# core_v1.net
KiCad netlist of a schematic drawn in EAGLE
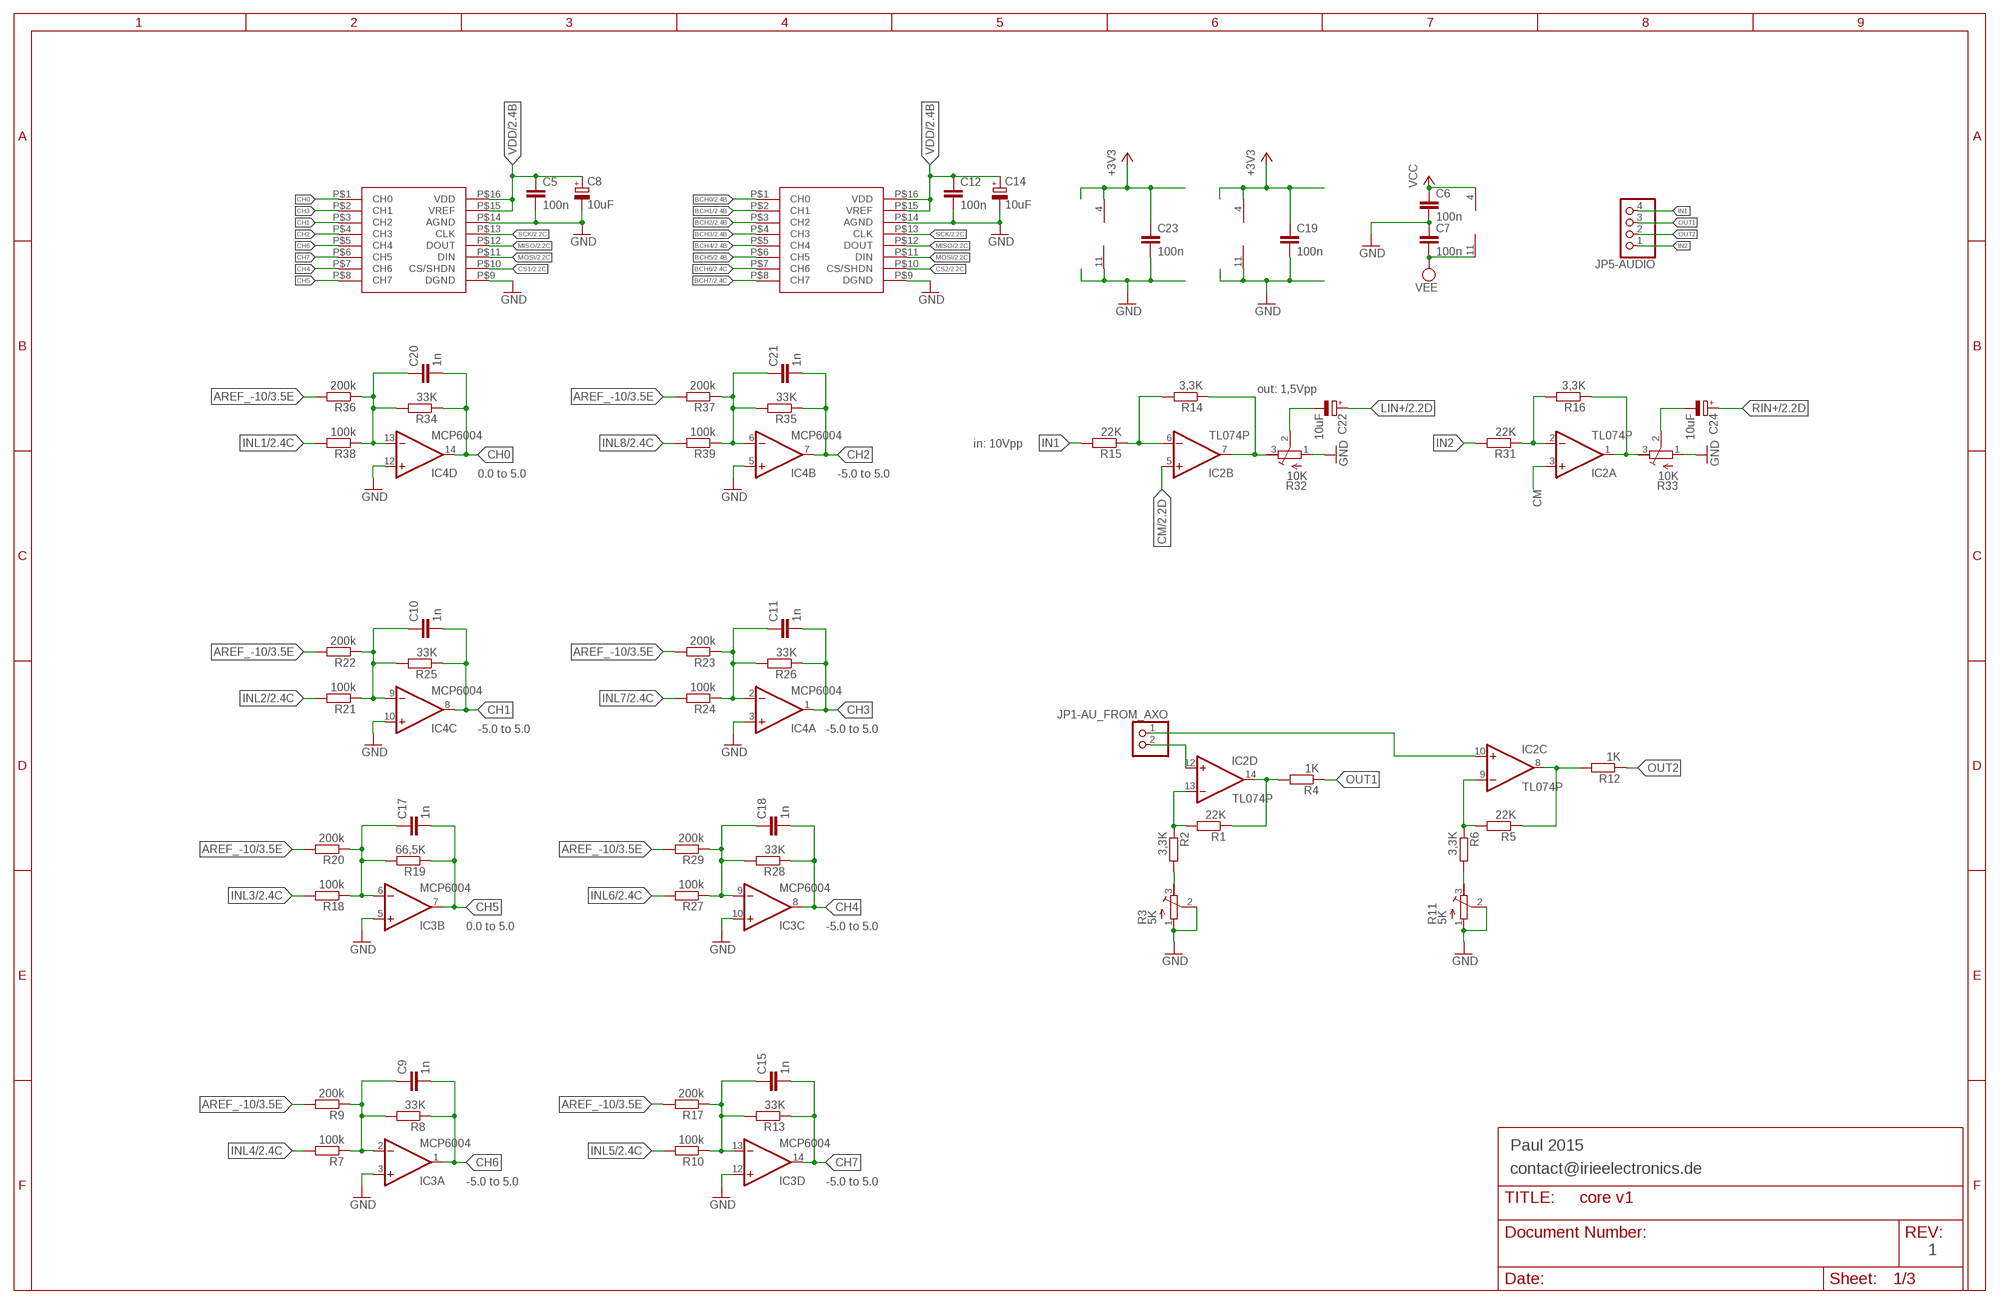
[diagram p0: schematic, sheet 1]
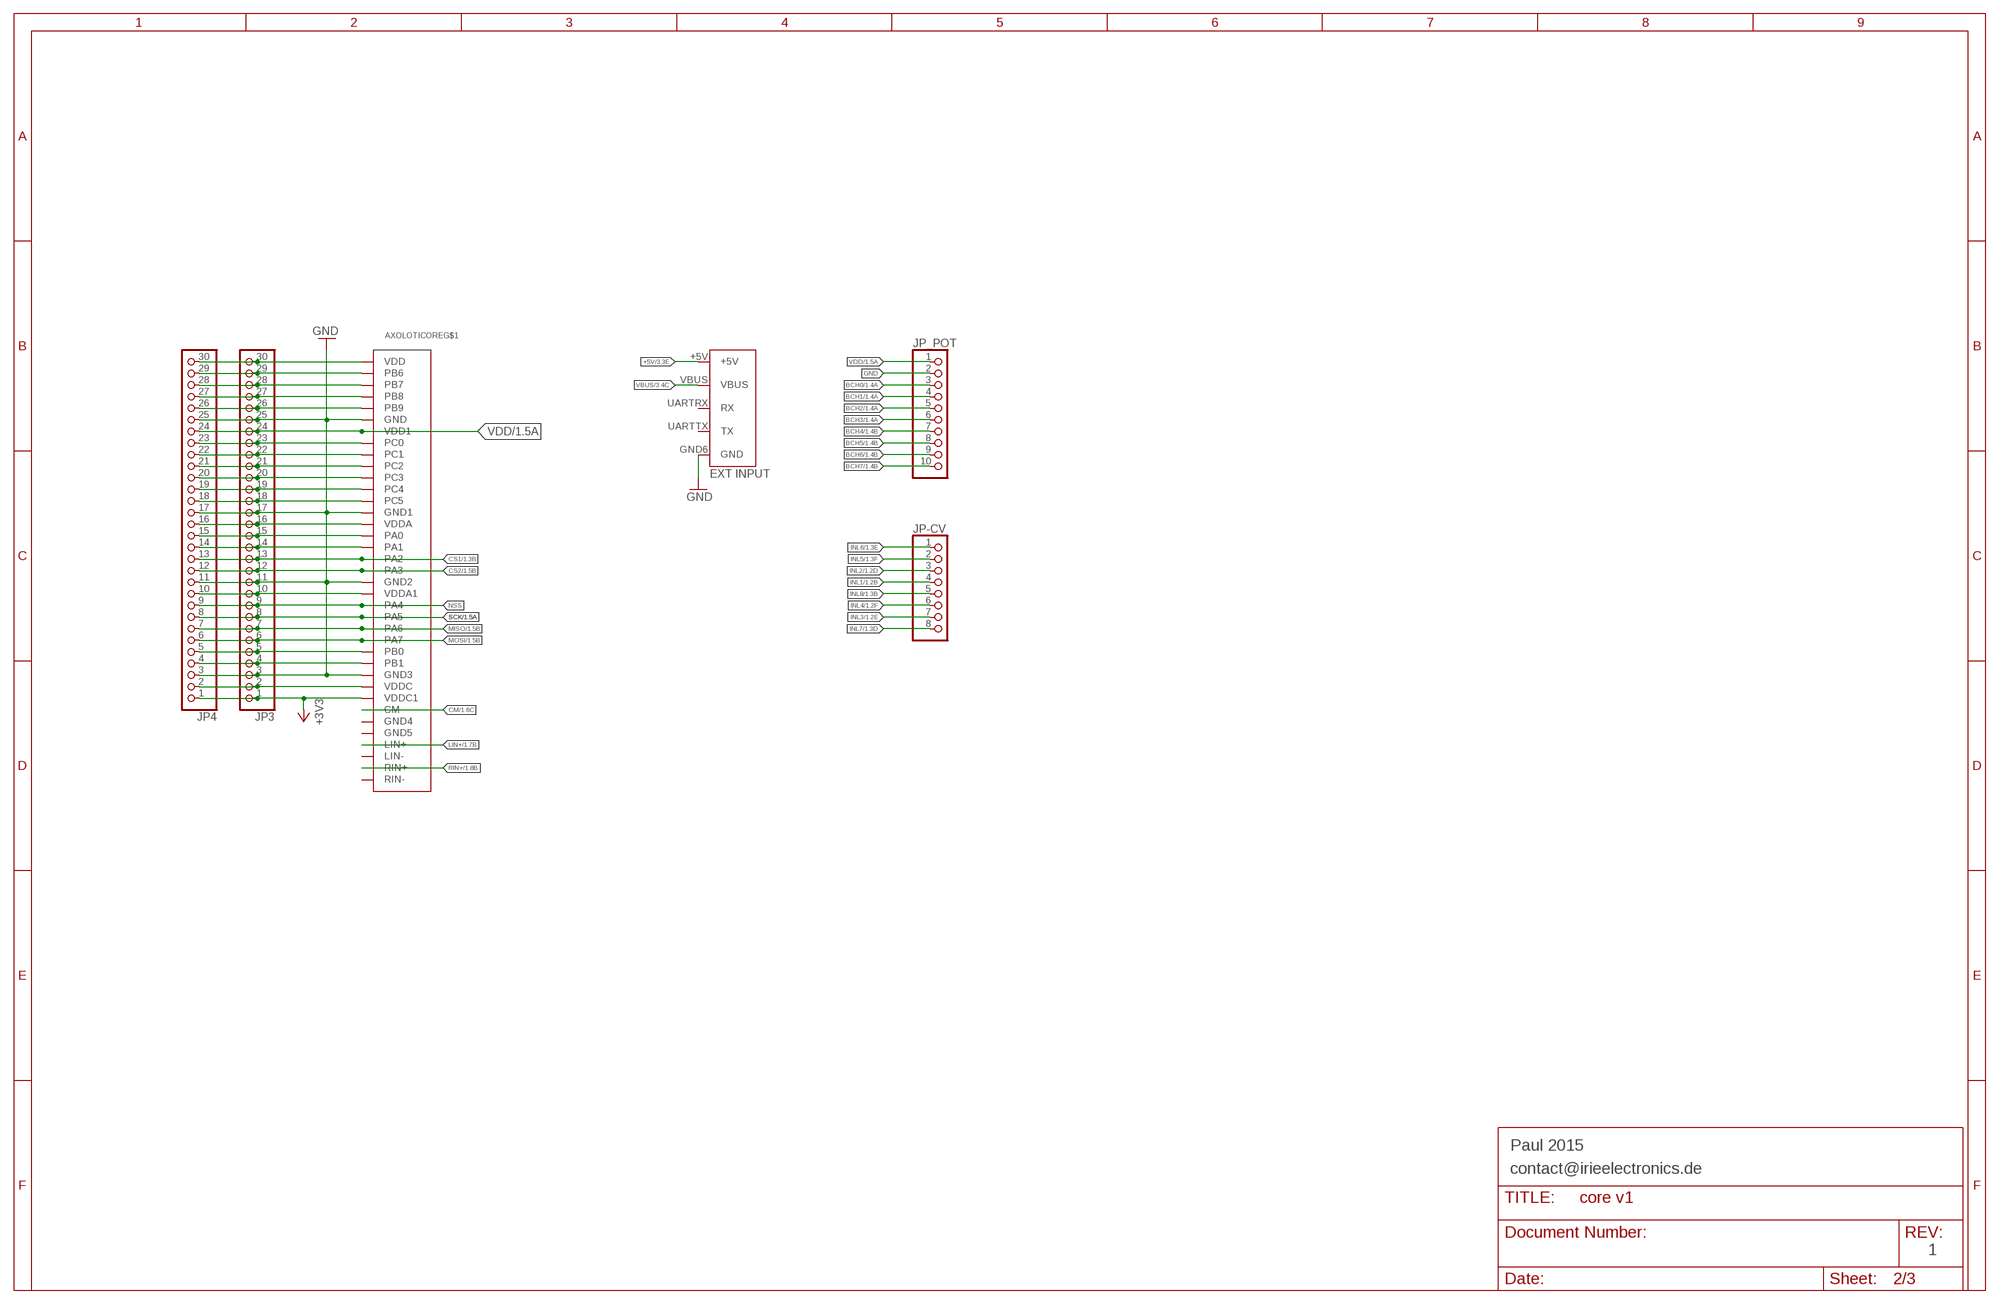
[diagram p1: schematic, sheet 2]
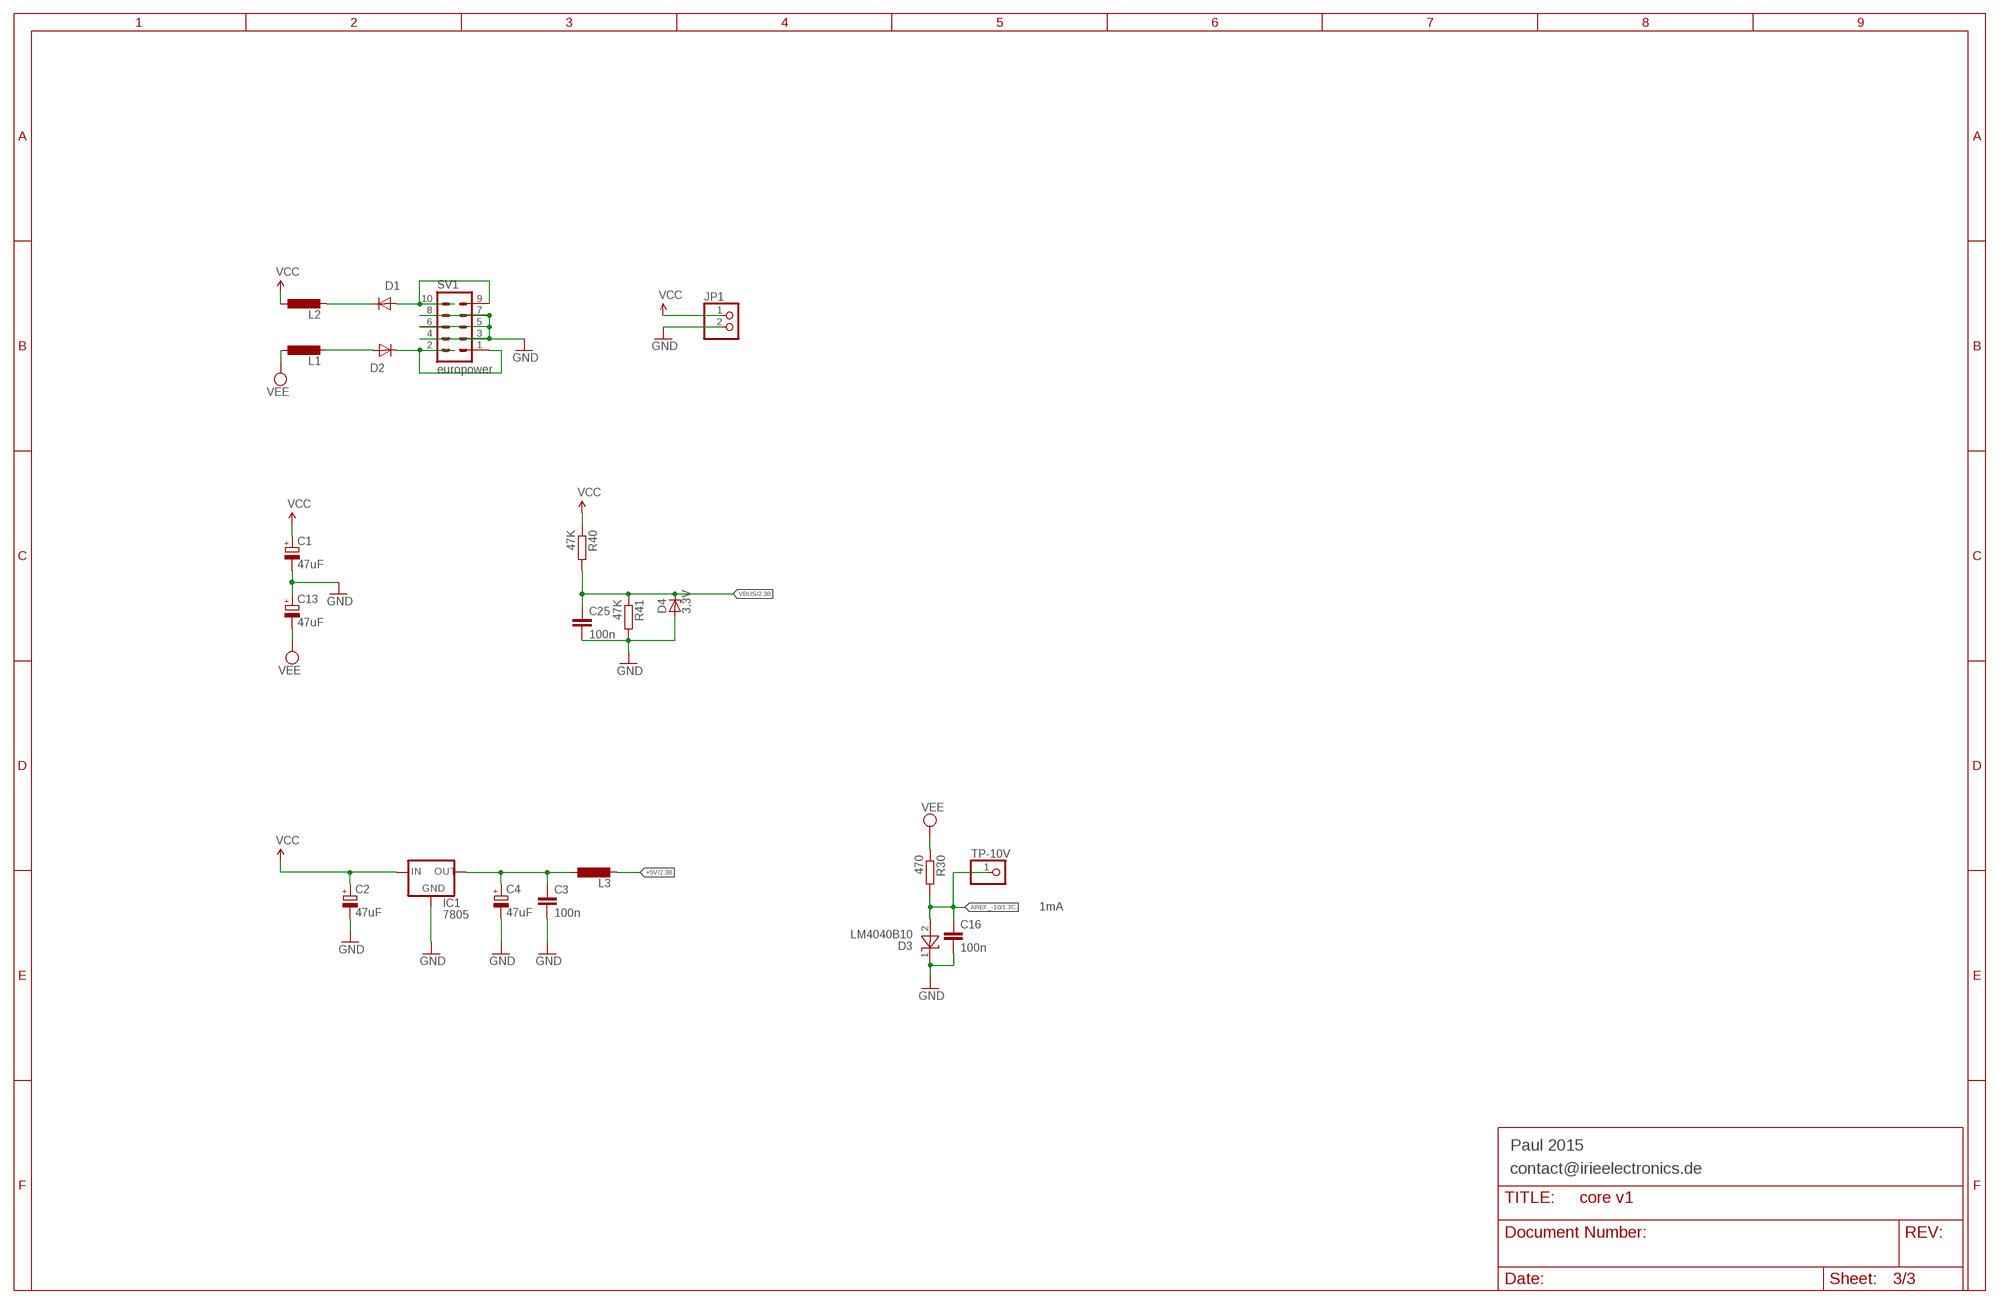
[diagram p2: schematic, sheet 3]

(export (version "E")
  (design (tool "Eeschema 10.0.6"))
  (components
    (comp (ref "AXOLOTICORE")
      (value "AXOLOTI-CORE")
      (footprint "eagle-import:AXOLOTI-CORE")
      (libsource (lib "eagle-import") (part "AXOLOTI-CORE"))
    )
    (comp (ref "JP-CV")
      (value "PINHD-1X8_2.54")
      (footprint "eagle-import:1X08")
      (libsource (lib "eagle-import") (part "PINHD-1X8_2.54"))
    )
    (comp (ref "JP3")
      (value "PINHD-1X30")
      (footprint "eagle-import:1X30")
      (libsource (lib "eagle-import") (part "PINHD-1X30"))
    )
    (comp (ref "JP4")
      (value "PINHD-1X30")
      (footprint "eagle-import:1X30")
      (libsource (lib "eagle-import") (part "PINHD-1X30"))
    )
    (comp (ref "JP_POT")
      (value "PINHD-1X10")
      (footprint "eagle-import:1X10")
      (libsource (lib "eagle-import") (part "PINHD-1X10"))
    )
    (comp (ref "C1")
      (value "47uF")
      (footprint "eagle-import:E2-5")
      (libsource (lib "eagle-import") (part "CPOL-EUE2-5"))
    )
    (comp (ref "C2")
      (value "47uF")
      (footprint "eagle-import:E2-5")
      (libsource (lib "eagle-import") (part "CPOL-EUE2-5"))
    )
    (comp (ref "C3")
      (value "100n")
      (footprint "eagle-import:C025-025X050")
      (libsource (lib "eagle-import") (part "C-EU025-025X050"))
    )
    (comp (ref "C4")
      (value "47uF")
      (footprint "eagle-import:E2,5-5")
      (libsource (lib "eagle-import") (part "CPOL-EUE2.5-5"))
    )
    (comp (ref "C13")
      (value "47uF")
      (footprint "eagle-import:E2-5")
      (libsource (lib "eagle-import") (part "CPOL-EUE2-5"))
    )
    (comp (ref "C16")
      (value "100n")
      (footprint "eagle-import:C025-025X050")
      (libsource (lib "eagle-import") (part "C-EU025-025X050"))
    )
    (comp (ref "C25")
      (value "100n")
      (footprint "eagle-import:C025-025X050")
      (libsource (lib "eagle-import") (part "C-EU025-025X050"))
    )
    (comp (ref "D1")
      (value "1N5819HW")
      (footprint "eagle-import:DO35-10")
      (libsource (lib "eagle-import") (part "1N4148DO35-10"))
    )
    (comp (ref "D2")
      (value "1N5819HW")
      (footprint "eagle-import:DO35-10")
      (libsource (lib "eagle-import") (part "1N4148DO35-10"))
    )
    (comp (ref "D3")
      (value "LM4040B10")
      (footprint "eagle-import:TO-92")
      (libsource (lib "eagle-import") (part "LM4040DIP"))
    )
    (comp (ref "D4")
      (value "3,3V")
      (footprint "eagle-import:DO35Z10")
      (libsource (lib "eagle-import") (part "1N821"))
    )
    (comp (ref "IC1")
      (value "7805")
      (footprint "eagle-import:78XXS")
      (libsource (lib "eagle-import") (part "78XXS"))
    )
    (comp (ref "JP1")
      (value "PINHD-1X2")
      (footprint "eagle-import:1X02")
      (libsource (lib "eagle-import") (part "PINHD-1X2"))
    )
    (comp (ref "L1")
      (value "L-EU0207/10")
      (footprint "eagle-import:0207_10")
      (libsource (lib "eagle-import") (part "L-EU0207/10"))
    )
    (comp (ref "L2")
      (value "L-EU0207/10")
      (footprint "eagle-import:0207_10")
      (libsource (lib "eagle-import") (part "L-EU0207/10"))
    )
    (comp (ref "L3")
      (value "L-EU0207/10")
      (footprint "eagle-import:0207_10")
      (libsource (lib "eagle-import") (part "L-EU0207/10"))
    )
    (comp (ref "R30")
      (value "470")
      (footprint "eagle-import:0207_12")
      (libsource (lib "eagle-import") (part "R-EU_0207/12"))
    )
    (comp (ref "R40")
      (value "47K")
      (footprint "eagle-import:0207_7")
      (libsource (lib "eagle-import") (part "R-EU_0207/7"))
    )
    (comp (ref "R41")
      (value "47K")
      (footprint "eagle-import:0207_7")
      (libsource (lib "eagle-import") (part "R-EU_0207/7"))
    )
    (comp (ref "SV1")
      (value "europower")
      (footprint "eagle-import:EURO_PWR_HEADER_FAT")
      (libsource (lib "eagle-import") (part "EURO_POWER_HEADERFAT_PADS"))
    )
    (comp (ref "TP-10V")
      (value "PINHD-1X1_2.54")
      (footprint "eagle-import:1X01")
      (libsource (lib "eagle-import") (part "PINHD-1X1_2.54"))
    )
    (comp (ref "C5")
      (value "100n")
      (footprint "eagle-import:C025-025X050")
      (libsource (lib "eagle-import") (part "C-EU025-025X050"))
    )
    (comp (ref "C6")
      (value "100n")
      (footprint "eagle-import:C025-025X050")
      (libsource (lib "eagle-import") (part "C-EU025-025X050"))
    )
    (comp (ref "C7")
      (value "100n")
      (footprint "eagle-import:C025-025X050")
      (libsource (lib "eagle-import") (part "C-EU025-025X050"))
    )
    (comp (ref "C8")
      (value "10uF")
      (footprint "eagle-import:E1,8-4")
      (libsource (lib "eagle-import") (part "CPOL-EUE1.8-4"))
    )
    (comp (ref "C9")
      (value "1n")
      (footprint "eagle-import:C050-025X075")
      (libsource (lib "eagle-import") (part "C-EU050-025X075"))
    )
    (comp (ref "C10")
      (value "1n")
      (footprint "eagle-import:C050-025X075")
      (libsource (lib "eagle-import") (part "C-EU050-025X075"))
    )
    (comp (ref "C11")
      (value "1n")
      (footprint "eagle-import:C050-025X075")
      (libsource (lib "eagle-import") (part "C-EU050-025X075"))
    )
    (comp (ref "C12")
      (value "100n")
      (footprint "eagle-import:C025-025X050")
      (libsource (lib "eagle-import") (part "C-EU025-025X050"))
    )
    (comp (ref "C14")
      (value "10uF")
      (footprint "eagle-import:E1,8-4")
      (libsource (lib "eagle-import") (part "CPOL-EUE1.8-4"))
    )
    (comp (ref "C15")
      (value "1n")
      (footprint "eagle-import:C050-025X075")
      (libsource (lib "eagle-import") (part "C-EU050-025X075"))
    )
    (comp (ref "C17")
      (value "1n")
      (footprint "eagle-import:C050-025X075")
      (libsource (lib "eagle-import") (part "C-EU050-025X075"))
    )
    (comp (ref "C18")
      (value "1n")
      (footprint "eagle-import:C050-025X075")
      (libsource (lib "eagle-import") (part "C-EU050-025X075"))
    )
    (comp (ref "C19")
      (value "100n")
      (footprint "eagle-import:C025-025X050")
      (libsource (lib "eagle-import") (part "C-EU025-025X050"))
    )
    (comp (ref "C20")
      (value "1n")
      (footprint "eagle-import:C050-025X075")
      (libsource (lib "eagle-import") (part "C-EU050-025X075"))
    )
    (comp (ref "C21")
      (value "1n")
      (footprint "eagle-import:C050-025X075")
      (libsource (lib "eagle-import") (part "C-EU050-025X075"))
    )
    (comp (ref "C22")
      (value "10uF")
      (footprint "eagle-import:E1,8-4")
      (libsource (lib "eagle-import") (part "CPOL-EUE1.8-4"))
    )
    (comp (ref "C23")
      (value "100n")
      (footprint "eagle-import:C025-025X050")
      (libsource (lib "eagle-import") (part "C-EU025-025X050"))
    )
    (comp (ref "C24")
      (value "10uF")
      (footprint "eagle-import:E1,8-4")
      (libsource (lib "eagle-import") (part "CPOL-EUE1.8-4"))
    )
    (comp (ref "IC2")
      (value "TL074P")
      (footprint "eagle-import:DIL14")
      (libsource (lib "eagle-import") (part "TL074P"))
    )
    (comp (ref "IC3")
      (value "MCP6004")
      (footprint "eagle-import:DIL14")
      (libsource (lib "eagle-import") (part "TL074P"))
    )
    (comp (ref "IC4")
      (value "MCP6004")
      (footprint "eagle-import:DIL14")
      (libsource (lib "eagle-import") (part "TL074P"))
    )
    (comp (ref "JP1-AU_FROM_AXO")
      (value "PINHD-1X2/90")
      (footprint "eagle-import:1X02_90")
      (libsource (lib "eagle-import") (part "PINHD-1X2/90"))
    )
    (comp (ref "JP5-AUDIO")
      (value "PINHD-1X4_2.54")
      (footprint "eagle-import:1X04")
      (libsource (lib "eagle-import") (part "PINHD-1X4_2.54"))
    )
    (comp (ref "R1")
      (value "22K")
      (footprint "eagle-import:0207_10")
      (libsource (lib "eagle-import") (part "R-EU_0207/10"))
    )
    (comp (ref "R2")
      (value "3,3K")
      (footprint "eagle-import:0207_12")
      (libsource (lib "eagle-import") (part "R-EU_0207/12"))
    )
    (comp (ref "R3")
      (value "5K")
      (footprint "eagle-import:RTRIM3296P")
      (libsource (lib "eagle-import") (part "R-TRIMM3296P"))
    )
    (comp (ref "R4")
      (value "1K")
      (footprint "eagle-import:0207_7")
      (libsource (lib "eagle-import") (part "R-EU_0207/7"))
    )
    (comp (ref "R5")
      (value "22K")
      (footprint "eagle-import:0207_7")
      (libsource (lib "eagle-import") (part "R-EU_0207/7"))
    )
    (comp (ref "R6")
      (value "3,3K")
      (footprint "eagle-import:0207_7")
      (libsource (lib "eagle-import") (part "R-EU_0207/7"))
    )
    (comp (ref "R7")
      (value "100k")
      (footprint "eagle-import:0207_7")
      (libsource (lib "eagle-import") (part "R-EU_0207/7"))
    )
    (comp (ref "R8")
      (value "33K")
      (footprint "eagle-import:0207_7")
      (libsource (lib "eagle-import") (part "R-EU_0207/7"))
    )
    (comp (ref "R9")
      (value "200k")
      (footprint "eagle-import:0207_10")
      (libsource (lib "eagle-import") (part "R-EU_0207/10"))
    )
    (comp (ref "R10")
      (value "100k")
      (footprint "eagle-import:0207_7")
      (libsource (lib "eagle-import") (part "R-EU_0207/7"))
    )
    (comp (ref "R11")
      (value "5K")
      (footprint "eagle-import:RTRIM3296P")
      (libsource (lib "eagle-import") (part "R-TRIMM3296P"))
    )
    (comp (ref "R12")
      (value "1K")
      (footprint "eagle-import:0207_10")
      (libsource (lib "eagle-import") (part "R-EU_0207/10"))
    )
    (comp (ref "R13")
      (value "33K")
      (footprint "eagle-import:0207_7")
      (libsource (lib "eagle-import") (part "R-EU_0207/7"))
    )
    (comp (ref "R14")
      (value "3,3K")
      (footprint "eagle-import:0207_7")
      (libsource (lib "eagle-import") (part "R-EU_0207/7"))
    )
    (comp (ref "R15")
      (value "22K")
      (footprint "eagle-import:0207_7")
      (libsource (lib "eagle-import") (part "R-EU_0207/7"))
    )
    (comp (ref "R16")
      (value "3,3K")
      (footprint "eagle-import:0207_7")
      (libsource (lib "eagle-import") (part "R-EU_0207/7"))
    )
    (comp (ref "R17")
      (value "200k")
      (footprint "eagle-import:0207_7")
      (libsource (lib "eagle-import") (part "R-EU_0207/7"))
    )
    (comp (ref "R18")
      (value "100k")
      (footprint "eagle-import:0207_7")
      (libsource (lib "eagle-import") (part "R-EU_0207/7"))
    )
    (comp (ref "R19")
      (value "66,5K")
      (footprint "eagle-import:0207_7")
      (libsource (lib "eagle-import") (part "R-EU_0207/7"))
    )
    (comp (ref "R20")
      (value "200k")
      (footprint "eagle-import:0207_10")
      (libsource (lib "eagle-import") (part "R-EU_0207/10"))
    )
    (comp (ref "R21")
      (value "100k")
      (footprint "eagle-import:0207_7")
      (libsource (lib "eagle-import") (part "R-EU_0207/7"))
    )
    (comp (ref "R22")
      (value "200k")
      (footprint "eagle-import:0207_7")
      (libsource (lib "eagle-import") (part "R-EU_0207/7"))
    )
    (comp (ref "R23")
      (value "200k")
      (footprint "eagle-import:0207_7")
      (libsource (lib "eagle-import") (part "R-EU_0207/7"))
    )
    (comp (ref "R24")
      (value "100k")
      (footprint "eagle-import:0207_10")
      (libsource (lib "eagle-import") (part "R-EU_0207/10"))
    )
    (comp (ref "R25")
      (value "33K")
      (footprint "eagle-import:0207_7")
      (libsource (lib "eagle-import") (part "R-EU_0207/7"))
    )
    (comp (ref "R26")
      (value "33K")
      (footprint "eagle-import:0207_7")
      (libsource (lib "eagle-import") (part "R-EU_0207/7"))
    )
    (comp (ref "R27")
      (value "100k")
      (footprint "eagle-import:0207_7")
      (libsource (lib "eagle-import") (part "R-EU_0207/7"))
    )
    (comp (ref "R28")
      (value "33K")
      (footprint "eagle-import:0207_7")
      (libsource (lib "eagle-import") (part "R-EU_0207/7"))
    )
    (comp (ref "R29")
      (value "200k")
      (footprint "eagle-import:0207_7")
      (libsource (lib "eagle-import") (part "R-EU_0207/7"))
    )
    (comp (ref "R31")
      (value "22K")
      (footprint "eagle-import:0207_7")
      (libsource (lib "eagle-import") (part "R-EU_0207/7"))
    )
    (comp (ref "R32")
      (value "10K")
      (footprint "eagle-import:RTRIM3296P")
      (libsource (lib "eagle-import") (part "R-TRIMM3296P"))
    )
    (comp (ref "R33")
      (value "10K")
      (footprint "eagle-import:RTRIM3296P")
      (libsource (lib "eagle-import") (part "R-TRIMM3296P"))
    )
    (comp (ref "R34")
      (value "33K")
      (footprint "eagle-import:0207_7")
      (libsource (lib "eagle-import") (part "R-EU_0207/7"))
    )
    (comp (ref "R35")
      (value "33K")
      (footprint "eagle-import:0207_7")
      (libsource (lib "eagle-import") (part "R-EU_0207/7"))
    )
    (comp (ref "R36")
      (value "200k")
      (footprint "eagle-import:0207_7")
      (libsource (lib "eagle-import") (part "R-EU_0207/7"))
    )
    (comp (ref "R37")
      (value "200k")
      (footprint "eagle-import:0207_7")
      (libsource (lib "eagle-import") (part "R-EU_0207/7"))
    )
    (comp (ref "R38")
      (value "100k")
      (footprint "eagle-import:0207_7")
      (libsource (lib "eagle-import") (part "R-EU_0207/7"))
    )
    (comp (ref "R39")
      (value "100k")
      (footprint "eagle-import:0207_7")
      (libsource (lib "eagle-import") (part "R-EU_0207/7"))
    )
    (comp (ref "U$4")
      (value "MCP3208_DIP")
      (footprint "eagle-import:MCP2308")
      (libsource (lib "eagle-import") (part "MCP3208_DIP"))
    )
    (comp (ref "U$5")
      (value "MCP3208_DIP")
      (footprint "eagle-import:MCP2308")
      (libsource (lib "eagle-import") (part "MCP3208_DIP"))
    )
  )
  (nets
    (net (code "1") (name "+3V3") (class "Default")
      (node (ref "AXOLOTICORE") (pin "VDDC1") (pinfunction "VDDC1_VDDC1") (pintype "bidirectional"))
      (node (ref "C19") (pin "1") (pinfunction "1_1") (pintype "passive"))
      (node (ref "C23") (pin "1") (pinfunction "1_1") (pintype "passive"))
      (node (ref "IC3") (pin "4") (pinfunction "V+_4") (pintype "power_in"))
      (node (ref "IC4") (pin "4") (pinfunction "V+_4") (pintype "power_in"))
      (node (ref "JP3") (pin "1") (pinfunction "1_1") (pintype "passive"))
      (node (ref "JP4") (pin "1") (pinfunction "1_1") (pintype "passive"))
    )
    (net (code "2") (name "+5V") (class "Default")
      (node (ref "AXOLOTICORE") (pin "+5V") (pinfunction "+5V_+5V") (pintype "bidirectional"))
      (node (ref "L3") (pin "2") (pinfunction "2_2") (pintype "passive"))
    )
    (net (code "3") (name "AREF_-10") (class "Default")
      (node (ref "C16") (pin "1") (pinfunction "1_1") (pintype "passive"))
      (node (ref "D3") (pin "2") (pinfunction "A_2") (pintype "output"))
      (node (ref "R17") (pin "2") (pinfunction "2_2") (pintype "passive"))
      (node (ref "R20") (pin "2") (pinfunction "2_2") (pintype "passive"))
      (node (ref "R22") (pin "2") (pinfunction "2_2") (pintype "passive"))
      (node (ref "R23") (pin "2") (pinfunction "2_2") (pintype "passive"))
      (node (ref "R29") (pin "2") (pinfunction "2_2") (pintype "passive"))
      (node (ref "R30") (pin "2") (pinfunction "2_2") (pintype "passive"))
      (node (ref "R36") (pin "2") (pinfunction "2_2") (pintype "passive"))
      (node (ref "R37") (pin "2") (pinfunction "2_2") (pintype "passive"))
      (node (ref "R9") (pin "2") (pinfunction "2_2") (pintype "passive"))
      (node (ref "TP-10V") (pin "1") (pinfunction "1_1") (pintype "passive"))
    )
    (net (code "4") (name "BCH0") (class "Default")
      (node (ref "JP_POT") (pin "3") (pinfunction "3_3") (pintype "passive"))
      (node (ref "U$5") (pin "P$1") (pinfunction "CH0_P$1") (pintype "bidirectional"))
    )
    (net (code "5") (name "BCH1") (class "Default")
      (node (ref "JP_POT") (pin "4") (pinfunction "4_4") (pintype "passive"))
      (node (ref "U$5") (pin "P$2") (pinfunction "CH1_P$2") (pintype "bidirectional"))
    )
    (net (code "6") (name "BCH2") (class "Default")
      (node (ref "JP_POT") (pin "5") (pinfunction "5_5") (pintype "passive"))
      (node (ref "U$5") (pin "P$3") (pinfunction "CH2_P$3") (pintype "bidirectional"))
    )
    (net (code "7") (name "BCH3") (class "Default")
      (node (ref "JP_POT") (pin "6") (pinfunction "6_6") (pintype "passive"))
      (node (ref "U$5") (pin "P$4") (pinfunction "CH3_P$4") (pintype "bidirectional"))
    )
    (net (code "8") (name "BCH4") (class "Default")
      (node (ref "JP_POT") (pin "7") (pinfunction "7_7") (pintype "passive"))
      (node (ref "U$5") (pin "P$5") (pinfunction "CH4_P$5") (pintype "bidirectional"))
    )
    (net (code "9") (name "BCH5") (class "Default")
      (node (ref "JP_POT") (pin "8") (pinfunction "8_8") (pintype "passive"))
      (node (ref "U$5") (pin "P$6") (pinfunction "CH5_P$6") (pintype "bidirectional"))
    )
    (net (code "10") (name "BCH6") (class "Default")
      (node (ref "JP_POT") (pin "9") (pinfunction "9_9") (pintype "passive"))
      (node (ref "U$5") (pin "P$7") (pinfunction "CH6_P$7") (pintype "bidirectional"))
    )
    (net (code "11") (name "BCH7") (class "Default")
      (node (ref "JP_POT") (pin "10") (pinfunction "10_10") (pintype "passive"))
      (node (ref "U$5") (pin "P$8") (pinfunction "CH7_P$8") (pintype "bidirectional"))
    )
    (net (code "12") (name "CH0") (class "Default")
      (node (ref "C20") (pin "2") (pinfunction "2_2") (pintype "passive"))
      (node (ref "IC4") (pin "14") (pinfunction "OUT_14") (pintype "output"))
      (node (ref "R34") (pin "1") (pinfunction "1_1") (pintype "passive"))
      (node (ref "U$4") (pin "P$1") (pinfunction "CH0_P$1") (pintype "bidirectional"))
    )
    (net (code "13") (name "CH1") (class "Default")
      (node (ref "C10") (pin "2") (pinfunction "2_2") (pintype "passive"))
      (node (ref "IC4") (pin "8") (pinfunction "OUT_8") (pintype "output"))
      (node (ref "R25") (pin "1") (pinfunction "1_1") (pintype "passive"))
      (node (ref "U$4") (pin "P$3") (pinfunction "CH2_P$3") (pintype "bidirectional"))
    )
    (net (code "14") (name "CH2") (class "Default")
      (node (ref "C21") (pin "2") (pinfunction "2_2") (pintype "passive"))
      (node (ref "IC4") (pin "7") (pinfunction "OUT_7") (pintype "output"))
      (node (ref "R35") (pin "1") (pinfunction "1_1") (pintype "passive"))
      (node (ref "U$4") (pin "P$4") (pinfunction "CH3_P$4") (pintype "bidirectional"))
    )
    (net (code "15") (name "CH3") (class "Default")
      (node (ref "C11") (pin "2") (pinfunction "2_2") (pintype "passive"))
      (node (ref "IC4") (pin "1") (pinfunction "OUT_1") (pintype "output"))
      (node (ref "R26") (pin "1") (pinfunction "1_1") (pintype "passive"))
      (node (ref "U$4") (pin "P$2") (pinfunction "CH1_P$2") (pintype "bidirectional"))
    )
    (net (code "16") (name "CH4") (class "Default")
      (node (ref "C18") (pin "2") (pinfunction "2_2") (pintype "passive"))
      (node (ref "IC3") (pin "8") (pinfunction "OUT_8") (pintype "output"))
      (node (ref "R28") (pin "1") (pinfunction "1_1") (pintype "passive"))
      (node (ref "U$4") (pin "P$7") (pinfunction "CH6_P$7") (pintype "bidirectional"))
    )
    (net (code "17") (name "CH5") (class "Default")
      (node (ref "C17") (pin "2") (pinfunction "2_2") (pintype "passive"))
      (node (ref "IC3") (pin "7") (pinfunction "OUT_7") (pintype "output"))
      (node (ref "R19") (pin "1") (pinfunction "1_1") (pintype "passive"))
      (node (ref "U$4") (pin "P$8") (pinfunction "CH7_P$8") (pintype "bidirectional"))
    )
    (net (code "18") (name "CH6") (class "Default")
      (node (ref "C9") (pin "2") (pinfunction "2_2") (pintype "passive"))
      (node (ref "IC3") (pin "1") (pinfunction "OUT_1") (pintype "output"))
      (node (ref "R8") (pin "1") (pinfunction "1_1") (pintype "passive"))
      (node (ref "U$4") (pin "P$5") (pinfunction "CH4_P$5") (pintype "bidirectional"))
    )
    (net (code "19") (name "CH7") (class "Default")
      (node (ref "C15") (pin "2") (pinfunction "2_2") (pintype "passive"))
      (node (ref "IC3") (pin "14") (pinfunction "OUT_14") (pintype "output"))
      (node (ref "R13") (pin "1") (pinfunction "1_1") (pintype "passive"))
      (node (ref "U$4") (pin "P$6") (pinfunction "CH5_P$6") (pintype "bidirectional"))
    )
    (net (code "20") (name "CM") (class "Default")
      (node (ref "AXOLOTICORE") (pin "CM") (pinfunction "CM_CM") (pintype "bidirectional"))
      (node (ref "IC2") (pin "3") (pinfunction "+IN_3") (pintype "input"))
      (node (ref "IC2") (pin "5") (pinfunction "+IN_5") (pintype "input"))
    )
    (net (code "21") (name "CS1") (class "Default")
      (node (ref "AXOLOTICORE") (pin "PA2") (pinfunction "PA2_PA2") (pintype "bidirectional"))
      (node (ref "JP3") (pin "13") (pinfunction "13_13") (pintype "passive"))
      (node (ref "JP4") (pin "13") (pinfunction "13_13") (pintype "passive"))
      (node (ref "U$4") (pin "P$10") (pinfunction "CS/SHDN_P$10") (pintype "bidirectional"))
    )
    (net (code "22") (name "CS2") (class "Default")
      (node (ref "AXOLOTICORE") (pin "PA3") (pinfunction "PA3_PA3") (pintype "bidirectional"))
      (node (ref "JP3") (pin "12") (pinfunction "12_12") (pintype "passive"))
      (node (ref "JP4") (pin "12") (pinfunction "12_12") (pintype "passive"))
      (node (ref "U$5") (pin "P$10") (pinfunction "CS/SHDN_P$10") (pintype "bidirectional"))
    )
    (net (code "23") (name "GND") (class "Default")
      (node (ref "AXOLOTICORE") (pin "GND") (pinfunction "GND_GND") (pintype "bidirectional"))
      (node (ref "AXOLOTICORE") (pin "GND1") (pinfunction "GND1_GND1") (pintype "bidirectional"))
      (node (ref "AXOLOTICORE") (pin "GND2") (pinfunction "GND3_GND2") (pintype "bidirectional"))
      (node (ref "AXOLOTICORE") (pin "GND3") (pinfunction "GND2_GND3") (pintype "bidirectional"))
      (node (ref "AXOLOTICORE") (pin "GND6") (pinfunction "GND_GND6") (pintype "bidirectional"))
      (node (ref "C1") (pin "-") (pinfunction "-_-") (pintype "passive"))
      (node (ref "C12") (pin "2") (pinfunction "2_2") (pintype "passive"))
      (node (ref "C13") (pin "+") (pinfunction "+_+") (pintype "passive"))
      (node (ref "C14") (pin "-") (pinfunction "-_-") (pintype "passive"))
      (node (ref "C16") (pin "2") (pinfunction "2_2") (pintype "passive"))
      (node (ref "C19") (pin "2") (pinfunction "2_2") (pintype "passive"))
      (node (ref "C2") (pin "-") (pinfunction "-_-") (pintype "passive"))
      (node (ref "C23") (pin "2") (pinfunction "2_2") (pintype "passive"))
      (node (ref "C25") (pin "2") (pinfunction "2_2") (pintype "passive"))
      (node (ref "C3") (pin "2") (pinfunction "2_2") (pintype "passive"))
      (node (ref "C4") (pin "-") (pinfunction "-_-") (pintype "passive"))
      (node (ref "C5") (pin "2") (pinfunction "2_2") (pintype "passive"))
      (node (ref "C6") (pin "2") (pinfunction "2_2") (pintype "passive"))
      (node (ref "C7") (pin "1") (pinfunction "1_1") (pintype "passive"))
      (node (ref "C8") (pin "-") (pinfunction "-_-") (pintype "passive"))
      (node (ref "D3") (pin "1") (pinfunction "C_1") (pintype "input"))
      (node (ref "D4") (pin "A") (pinfunction "A_A") (pintype "passive"))
      (node (ref "IC1") (pin "GND") (pinfunction "GND_GND") (pintype "input"))
      (node (ref "IC3") (pin "10") (pinfunction "+IN_10") (pintype "input"))
      (node (ref "IC3") (pin "11") (pinfunction "V-_11") (pintype "power_in"))
      (node (ref "IC3") (pin "12") (pinfunction "+IN_12") (pintype "input"))
      (node (ref "IC3") (pin "3") (pinfunction "+IN_3") (pintype "input"))
      (node (ref "IC3") (pin "5") (pinfunction "+IN_5") (pintype "input"))
      (node (ref "IC4") (pin "10") (pinfunction "+IN_10") (pintype "input"))
      (node (ref "IC4") (pin "11") (pinfunction "V-_11") (pintype "power_in"))
      (node (ref "IC4") (pin "12") (pinfunction "+IN_12") (pintype "input"))
      (node (ref "IC4") (pin "3") (pinfunction "+IN_3") (pintype "input"))
      (node (ref "IC4") (pin "5") (pinfunction "+IN_5") (pintype "input"))
      (node (ref "JP1") (pin "2") (pinfunction "2_2") (pintype "passive"))
      (node (ref "JP3") (pin "11") (pinfunction "11_11") (pintype "passive"))
      (node (ref "JP3") (pin "17") (pinfunction "17_17") (pintype "passive"))
      (node (ref "JP3") (pin "25") (pinfunction "25_25") (pintype "passive"))
      (node (ref "JP3") (pin "3") (pinfunction "3_3") (pintype "passive"))
      (node (ref "JP4") (pin "11") (pinfunction "11_11") (pintype "passive"))
      (node (ref "JP4") (pin "17") (pinfunction "17_17") (pintype "passive"))
      (node (ref "JP4") (pin "25") (pinfunction "25_25") (pintype "passive"))
      (node (ref "JP4") (pin "3") (pinfunction "3_3") (pintype "passive"))
      (node (ref "JP_POT") (pin "2") (pinfunction "2_2") (pintype "passive"))
      (node (ref "R11") (pin "1") (pinfunction "E_1") (pintype "passive"))
      (node (ref "R11") (pin "2") (pinfunction "S_2") (pintype "passive"))
      (node (ref "R3") (pin "1") (pinfunction "E_1") (pintype "passive"))
      (node (ref "R3") (pin "2") (pinfunction "S_2") (pintype "passive"))
      (node (ref "R32") (pin "1") (pinfunction "E_1") (pintype "passive"))
      (node (ref "R33") (pin "1") (pinfunction "E_1") (pintype "passive"))
      (node (ref "R41") (pin "2") (pinfunction "2_2") (pintype "passive"))
      (node (ref "SV1") (pin "3") (pinfunction "3_3") (pintype "passive"))
      (node (ref "SV1") (pin "4") (pinfunction "4_4") (pintype "passive"))
      (node (ref "SV1") (pin "5") (pinfunction "5_5") (pintype "passive"))
      (node (ref "SV1") (pin "6") (pinfunction "6_6") (pintype "passive"))
      (node (ref "SV1") (pin "7") (pinfunction "7_7") (pintype "passive"))
      (node (ref "SV1") (pin "8") (pinfunction "8_8") (pintype "passive"))
      (node (ref "U$4") (pin "P$14") (pinfunction "AGND_P$14") (pintype "bidirectional"))
      (node (ref "U$4") (pin "P$9") (pinfunction "DGND_P$9") (pintype "bidirectional"))
      (node (ref "U$5") (pin "P$14") (pinfunction "AGND_P$14") (pintype "bidirectional"))
      (node (ref "U$5") (pin "P$9") (pinfunction "DGND_P$9") (pintype "bidirectional"))
    )
    (net (code "24") (name "IN1") (class "Default")
      (node (ref "JP5-AUDIO") (pin "4") (pinfunction "4_4") (pintype "passive"))
      (node (ref "R15") (pin "2") (pinfunction "2_2") (pintype "passive"))
    )
    (net (code "25") (name "IN2") (class "Default")
      (node (ref "JP5-AUDIO") (pin "1") (pinfunction "1_1") (pintype "passive"))
      (node (ref "R31") (pin "2") (pinfunction "2_2") (pintype "passive"))
    )
    (net (code "26") (name "INL1") (class "Default")
      (node (ref "JP-CV") (pin "4") (pinfunction "4_4") (pintype "passive"))
      (node (ref "R38") (pin "2") (pinfunction "2_2") (pintype "passive"))
    )
    (net (code "27") (name "INL2") (class "Default")
      (node (ref "JP-CV") (pin "3") (pinfunction "3_3") (pintype "passive"))
      (node (ref "R21") (pin "2") (pinfunction "2_2") (pintype "passive"))
    )
    (net (code "28") (name "INL3") (class "Default")
      (node (ref "JP-CV") (pin "7") (pinfunction "7_7") (pintype "passive"))
      (node (ref "R18") (pin "2") (pinfunction "2_2") (pintype "passive"))
    )
    (net (code "29") (name "INL4") (class "Default")
      (node (ref "JP-CV") (pin "6") (pinfunction "6_6") (pintype "passive"))
      (node (ref "R7") (pin "2") (pinfunction "2_2") (pintype "passive"))
    )
    (net (code "30") (name "INL5") (class "Default")
      (node (ref "JP-CV") (pin "2") (pinfunction "2_2") (pintype "passive"))
      (node (ref "R10") (pin "2") (pinfunction "2_2") (pintype "passive"))
    )
    (net (code "31") (name "INL6") (class "Default")
      (node (ref "JP-CV") (pin "1") (pinfunction "1_1") (pintype "passive"))
      (node (ref "R27") (pin "2") (pinfunction "2_2") (pintype "passive"))
    )
    (net (code "32") (name "INL7") (class "Default")
      (node (ref "JP-CV") (pin "8") (pinfunction "8_8") (pintype "passive"))
      (node (ref "R24") (pin "2") (pinfunction "2_2") (pintype "passive"))
    )
    (net (code "33") (name "INL8") (class "Default")
      (node (ref "JP-CV") (pin "5") (pinfunction "5_5") (pintype "passive"))
      (node (ref "R39") (pin "2") (pinfunction "2_2") (pintype "passive"))
    )
    (net (code "34") (name "LIN+") (class "Default")
      (node (ref "AXOLOTICORE") (pin "LIN+") (pinfunction "LIN+_LIN+") (pintype "bidirectional"))
      (node (ref "C22") (pin "+") (pinfunction "+_+") (pintype "passive"))
    )
    (net (code "35") (name "MISO") (class "Default")
      (node (ref "AXOLOTICORE") (pin "PA6") (pinfunction "PA6_PA6") (pintype "bidirectional"))
      (node (ref "JP3") (pin "7") (pinfunction "7_7") (pintype "passive"))
      (node (ref "JP4") (pin "7") (pinfunction "7_7") (pintype "passive"))
      (node (ref "U$4") (pin "P$12") (pinfunction "DOUT_P$12") (pintype "bidirectional"))
      (node (ref "U$5") (pin "P$12") (pinfunction "DOUT_P$12") (pintype "bidirectional"))
    )
    (net (code "36") (name "MOSI") (class "Default")
      (node (ref "AXOLOTICORE") (pin "PA7") (pinfunction "PA7_PA7") (pintype "bidirectional"))
      (node (ref "JP3") (pin "6") (pinfunction "6_6") (pintype "passive"))
      (node (ref "JP4") (pin "6") (pinfunction "6_6") (pintype "passive"))
      (node (ref "U$4") (pin "P$11") (pinfunction "DIN_P$11") (pintype "bidirectional"))
      (node (ref "U$5") (pin "P$11") (pinfunction "DIN_P$11") (pintype "bidirectional"))
    )
    (net (code "37") (name "NSS") (class "Default")
      (node (ref "AXOLOTICORE") (pin "PA4") (pinfunction "PA4_PA4") (pintype "bidirectional"))
      (node (ref "JP3") (pin "9") (pinfunction "9_9") (pintype "passive"))
      (node (ref "JP4") (pin "9") (pinfunction "9_9") (pintype "passive"))
    )
    (net (code "38") (name "Net-(AXOLOTICORE-PadPA0)") (class "Default")
      (node (ref "AXOLOTICORE") (pin "PA0") (pinfunction "PA0_PA0") (pintype "bidirectional"))
      (node (ref "JP3") (pin "15") (pinfunction "15_15") (pintype "passive"))
      (node (ref "JP4") (pin "15") (pinfunction "15_15") (pintype "passive"))
    )
    (net (code "39") (name "Net-(AXOLOTICORE-PadPA1)") (class "Default")
      (node (ref "AXOLOTICORE") (pin "PA1") (pinfunction "PA1_PA1") (pintype "bidirectional"))
      (node (ref "JP3") (pin "14") (pinfunction "14_14") (pintype "passive"))
      (node (ref "JP4") (pin "14") (pinfunction "14_14") (pintype "passive"))
    )
    (net (code "40") (name "Net-(AXOLOTICORE-PadPB0)") (class "Default")
      (node (ref "AXOLOTICORE") (pin "PB0") (pinfunction "PB0_PB0") (pintype "bidirectional"))
      (node (ref "JP3") (pin "5") (pinfunction "5_5") (pintype "passive"))
      (node (ref "JP4") (pin "5") (pinfunction "5_5") (pintype "passive"))
    )
    (net (code "41") (name "Net-(AXOLOTICORE-PadPB1)") (class "Default")
      (node (ref "AXOLOTICORE") (pin "PB1") (pinfunction "PB1_PB1") (pintype "bidirectional"))
      (node (ref "JP3") (pin "4") (pinfunction "4_4") (pintype "passive"))
      (node (ref "JP4") (pin "4") (pinfunction "4_4") (pintype "passive"))
    )
    (net (code "42") (name "Net-(AXOLOTICORE-PadPB6)") (class "Default")
      (node (ref "AXOLOTICORE") (pin "PB6") (pinfunction "PB6_PB6") (pintype "bidirectional"))
      (node (ref "JP3") (pin "29") (pinfunction "29_29") (pintype "passive"))
      (node (ref "JP4") (pin "29") (pinfunction "29_29") (pintype "passive"))
    )
    (net (code "43") (name "Net-(AXOLOTICORE-PadPB7)") (class "Default")
      (node (ref "AXOLOTICORE") (pin "PB7") (pinfunction "PB7_PB7") (pintype "bidirectional"))
      (node (ref "JP3") (pin "28") (pinfunction "28_28") (pintype "passive"))
      (node (ref "JP4") (pin "28") (pinfunction "28_28") (pintype "passive"))
    )
    (net (code "44") (name "Net-(AXOLOTICORE-PadPB8)") (class "Default")
      (node (ref "AXOLOTICORE") (pin "PB8") (pinfunction "PB8_PB8") (pintype "bidirectional"))
      (node (ref "JP3") (pin "27") (pinfunction "27_27") (pintype "passive"))
      (node (ref "JP4") (pin "27") (pinfunction "27_27") (pintype "passive"))
    )
    (net (code "45") (name "Net-(AXOLOTICORE-PadPB9)") (class "Default")
      (node (ref "AXOLOTICORE") (pin "PB9") (pinfunction "PB9_PB9") (pintype "bidirectional"))
      (node (ref "JP3") (pin "26") (pinfunction "26_26") (pintype "passive"))
      (node (ref "JP4") (pin "26") (pinfunction "26_26") (pintype "passive"))
    )
    (net (code "46") (name "Net-(AXOLOTICORE-PadPC0)") (class "Default")
      (node (ref "AXOLOTICORE") (pin "PC0") (pinfunction "PC0_PC0") (pintype "bidirectional"))
      (node (ref "JP3") (pin "23") (pinfunction "23_23") (pintype "passive"))
      (node (ref "JP4") (pin "23") (pinfunction "23_23") (pintype "passive"))
    )
    (net (code "47") (name "Net-(AXOLOTICORE-PadPC1)") (class "Default")
      (node (ref "AXOLOTICORE") (pin "PC1") (pinfunction "PC1_PC1") (pintype "bidirectional"))
      (node (ref "JP3") (pin "22") (pinfunction "22_22") (pintype "passive"))
      (node (ref "JP4") (pin "22") (pinfunction "22_22") (pintype "passive"))
    )
    (net (code "48") (name "Net-(AXOLOTICORE-PadPC2)") (class "Default")
      (node (ref "AXOLOTICORE") (pin "PC2") (pinfunction "PC2_PC2") (pintype "bidirectional"))
      (node (ref "JP3") (pin "21") (pinfunction "21_21") (pintype "passive"))
      (node (ref "JP4") (pin "21") (pinfunction "21_21") (pintype "passive"))
    )
    (net (code "49") (name "Net-(AXOLOTICORE-PadPC3)") (class "Default")
      (node (ref "AXOLOTICORE") (pin "PC3") (pinfunction "PC3_PC3") (pintype "bidirectional"))
      (node (ref "JP3") (pin "20") (pinfunction "20_20") (pintype "passive"))
      (node (ref "JP4") (pin "20") (pinfunction "20_20") (pintype "passive"))
    )
    (net (code "50") (name "Net-(AXOLOTICORE-PadPC4)") (class "Default")
      (node (ref "AXOLOTICORE") (pin "PC4") (pinfunction "PC4_PC4") (pintype "bidirectional"))
      (node (ref "JP3") (pin "19") (pinfunction "19_19") (pintype "passive"))
      (node (ref "JP4") (pin "19") (pinfunction "19_19") (pintype "passive"))
    )
    (net (code "51") (name "Net-(AXOLOTICORE-PadPC5)") (class "Default")
      (node (ref "AXOLOTICORE") (pin "PC5") (pinfunction "PC5_PC5") (pintype "bidirectional"))
      (node (ref "JP3") (pin "18") (pinfunction "18_18") (pintype "passive"))
      (node (ref "JP4") (pin "18") (pinfunction "18_18") (pintype "passive"))
    )
    (net (code "52") (name "Net-(AXOLOTICORE-PadVDD)") (class "Default")
      (node (ref "AXOLOTICORE") (pin "VDD") (pinfunction "VDD_VDD") (pintype "bidirectional"))
      (node (ref "JP3") (pin "30") (pinfunction "30_30") (pintype "passive"))
      (node (ref "JP4") (pin "30") (pinfunction "30_30") (pintype "passive"))
    )
    (net (code "53") (name "Net-(AXOLOTICORE-PadVDDA)") (class "Default")
      (node (ref "AXOLOTICORE") (pin "VDDA") (pinfunction "VDDA_VDDA") (pintype "bidirectional"))
      (node (ref "JP3") (pin "16") (pinfunction "16_16") (pintype "passive"))
      (node (ref "JP4") (pin "16") (pinfunction "16_16") (pintype "passive"))
    )
    (net (code "54") (name "Net-(AXOLOTICORE-PadVDDA1)") (class "Default")
      (node (ref "AXOLOTICORE") (pin "VDDA1") (pinfunction "VDDA1_VDDA1") (pintype "bidirectional"))
      (node (ref "JP3") (pin "10") (pinfunction "10_10") (pintype "passive"))
      (node (ref "JP4") (pin "10") (pinfunction "10_10") (pintype "passive"))
    )
    (net (code "55") (name "Net-(AXOLOTICORE-PadVDDC)") (class "Default")
      (node (ref "AXOLOTICORE") (pin "VDDC") (pinfunction "VDDC_VDDC") (pintype "bidirectional"))
      (node (ref "JP3") (pin "2") (pinfunction "2_2") (pintype "passive"))
      (node (ref "JP4") (pin "2") (pinfunction "2_2") (pintype "passive"))
    )
    (net (code "56") (name "Net-(C3-Pad1)") (class "Default")
      (node (ref "C3") (pin "1") (pinfunction "1_1") (pintype "passive"))
      (node (ref "C4") (pin "+") (pinfunction "+_+") (pintype "passive"))
      (node (ref "IC1") (pin "OUT") (pinfunction "OUT_OUT") (pintype "passive"))
      (node (ref "L3") (pin "1") (pinfunction "1_1") (pintype "passive"))
    )
    (net (code "57") (name "Net-(D1-PadA)") (class "Default")
      (node (ref "D1") (pin "A") (pinfunction "A_A") (pintype "passive"))
      (node (ref "SV1") (pin "10") (pinfunction "10_10") (pintype "passive"))
      (node (ref "SV1") (pin "9") (pinfunction "9_9") (pintype "passive"))
    )
    (net (code "58") (name "Net-(D1-PadC)") (class "Default")
      (node (ref "D1") (pin "C") (pinfunction "C_C") (pintype "passive"))
      (node (ref "L2") (pin "2") (pinfunction "2_2") (pintype "passive"))
    )
    (net (code "59") (name "Net-(D2-PadA)") (class "Default")
      (node (ref "D2") (pin "A") (pinfunction "A_A") (pintype "passive"))
      (node (ref "L1") (pin "2") (pinfunction "2_2") (pintype "passive"))
    )
    (net (code "60") (name "Net-(D2-PadC)") (class "Default")
      (node (ref "D2") (pin "C") (pinfunction "C_C") (pintype "passive"))
      (node (ref "SV1") (pin "1") (pinfunction "1_1") (pintype "passive"))
      (node (ref "SV1") (pin "2") (pinfunction "2_2") (pintype "passive"))
    )
    (net (code "61") (name "Net-(IC2A--IN)") (class "Default")
      (node (ref "IC2") (pin "2") (pinfunction "-IN_2") (pintype "input"))
      (node (ref "R16") (pin "2") (pinfunction "2_2") (pintype "passive"))
      (node (ref "R31") (pin "1") (pinfunction "1_1") (pintype "passive"))
    )
    (net (code "62") (name "Net-(IC2A-OUT)") (class "Default")
      (node (ref "IC2") (pin "1") (pinfunction "OUT_1") (pintype "output"))
      (node (ref "R16") (pin "1") (pinfunction "1_1") (pintype "passive"))
      (node (ref "R33") (pin "3") (pinfunction "A_3") (pintype "passive"))
    )
    (net (code "63") (name "Net-(IC2B--IN)") (class "Default")
      (node (ref "IC2") (pin "6") (pinfunction "-IN_6") (pintype "input"))
      (node (ref "R14") (pin "2") (pinfunction "2_2") (pintype "passive"))
      (node (ref "R15") (pin "1") (pinfunction "1_1") (pintype "passive"))
    )
    (net (code "64") (name "Net-(IC2B-OUT)") (class "Default")
      (node (ref "IC2") (pin "7") (pinfunction "OUT_7") (pintype "output"))
      (node (ref "R14") (pin "1") (pinfunction "1_1") (pintype "passive"))
      (node (ref "R32") (pin "3") (pinfunction "A_3") (pintype "passive"))
    )
    (net (code "65") (name "Net-(IC2C-+IN)") (class "Default")
      (node (ref "IC2") (pin "10") (pinfunction "+IN_10") (pintype "input"))
      (node (ref "JP1-AU_FROM_AXO") (pin "1") (pinfunction "1_1") (pintype "passive"))
    )
    (net (code "66") (name "Net-(IC2C--IN)") (class "Default")
      (node (ref "IC2") (pin "9") (pinfunction "-IN_9") (pintype "input"))
      (node (ref "R5") (pin "2") (pinfunction "2_2") (pintype "passive"))
      (node (ref "R6") (pin "1") (pinfunction "1_1") (pintype "passive"))
    )
    (net (code "67") (name "Net-(IC2C-OUT)") (class "Default")
      (node (ref "IC2") (pin "8") (pinfunction "OUT_8") (pintype "output"))
      (node (ref "R12") (pin "2") (pinfunction "2_2") (pintype "passive"))
      (node (ref "R5") (pin "1") (pinfunction "1_1") (pintype "passive"))
    )
    (net (code "68") (name "Net-(IC2D-+IN)") (class "Default")
      (node (ref "IC2") (pin "12") (pinfunction "+IN_12") (pintype "input"))
      (node (ref "JP1-AU_FROM_AXO") (pin "2") (pinfunction "2_2") (pintype "passive"))
    )
    (net (code "69") (name "Net-(IC2D--IN)") (class "Default")
      (node (ref "IC2") (pin "13") (pinfunction "-IN_13") (pintype "input"))
      (node (ref "R1") (pin "2") (pinfunction "2_2") (pintype "passive"))
      (node (ref "R2") (pin "1") (pinfunction "1_1") (pintype "passive"))
    )
    (net (code "70") (name "Net-(IC2D-OUT)") (class "Default")
      (node (ref "IC2") (pin "14") (pinfunction "OUT_14") (pintype "output"))
      (node (ref "R1") (pin "1") (pinfunction "1_1") (pintype "passive"))
      (node (ref "R4") (pin "2") (pinfunction "2_2") (pintype "passive"))
    )
    (net (code "71") (name "Net-(IC3A--IN)") (class "Default")
      (node (ref "C9") (pin "1") (pinfunction "1_1") (pintype "passive"))
      (node (ref "IC3") (pin "2") (pinfunction "-IN_2") (pintype "input"))
      (node (ref "R7") (pin "1") (pinfunction "1_1") (pintype "passive"))
      (node (ref "R8") (pin "2") (pinfunction "2_2") (pintype "passive"))
      (node (ref "R9") (pin "1") (pinfunction "1_1") (pintype "passive"))
    )
    (net (code "72") (name "Net-(IC3B--IN)") (class "Default")
      (node (ref "C17") (pin "1") (pinfunction "1_1") (pintype "passive"))
      (node (ref "IC3") (pin "6") (pinfunction "-IN_6") (pintype "input"))
      (node (ref "R18") (pin "1") (pinfunction "1_1") (pintype "passive"))
      (node (ref "R19") (pin "2") (pinfunction "2_2") (pintype "passive"))
      (node (ref "R20") (pin "1") (pinfunction "1_1") (pintype "passive"))
    )
    (net (code "73") (name "Net-(IC3C--IN)") (class "Default")
      (node (ref "C18") (pin "1") (pinfunction "1_1") (pintype "passive"))
      (node (ref "IC3") (pin "9") (pinfunction "-IN_9") (pintype "input"))
      (node (ref "R27") (pin "1") (pinfunction "1_1") (pintype "passive"))
      (node (ref "R28") (pin "2") (pinfunction "2_2") (pintype "passive"))
      (node (ref "R29") (pin "1") (pinfunction "1_1") (pintype "passive"))
    )
    (net (code "74") (name "Net-(IC3D--IN)") (class "Default")
      (node (ref "C15") (pin "1") (pinfunction "1_1") (pintype "passive"))
      (node (ref "IC3") (pin "13") (pinfunction "-IN_13") (pintype "input"))
      (node (ref "R10") (pin "1") (pinfunction "1_1") (pintype "passive"))
      (node (ref "R13") (pin "2") (pinfunction "2_2") (pintype "passive"))
      (node (ref "R17") (pin "1") (pinfunction "1_1") (pintype "passive"))
    )
    (net (code "75") (name "Net-(IC4A--IN)") (class "Default")
      (node (ref "C11") (pin "1") (pinfunction "1_1") (pintype "passive"))
      (node (ref "IC4") (pin "2") (pinfunction "-IN_2") (pintype "input"))
      (node (ref "R23") (pin "1") (pinfunction "1_1") (pintype "passive"))
      (node (ref "R24") (pin "1") (pinfunction "1_1") (pintype "passive"))
      (node (ref "R26") (pin "2") (pinfunction "2_2") (pintype "passive"))
    )
    (net (code "76") (name "Net-(IC4B--IN)") (class "Default")
      (node (ref "C21") (pin "1") (pinfunction "1_1") (pintype "passive"))
      (node (ref "IC4") (pin "6") (pinfunction "-IN_6") (pintype "input"))
      (node (ref "R35") (pin "2") (pinfunction "2_2") (pintype "passive"))
      (node (ref "R37") (pin "1") (pinfunction "1_1") (pintype "passive"))
      (node (ref "R39") (pin "1") (pinfunction "1_1") (pintype "passive"))
    )
    (net (code "77") (name "Net-(IC4C--IN)") (class "Default")
      (node (ref "C10") (pin "1") (pinfunction "1_1") (pintype "passive"))
      (node (ref "IC4") (pin "9") (pinfunction "-IN_9") (pintype "input"))
      (node (ref "R21") (pin "1") (pinfunction "1_1") (pintype "passive"))
      (node (ref "R22") (pin "1") (pinfunction "1_1") (pintype "passive"))
      (node (ref "R25") (pin "2") (pinfunction "2_2") (pintype "passive"))
    )
    (net (code "78") (name "Net-(IC4D--IN)") (class "Default")
      (node (ref "C20") (pin "1") (pinfunction "1_1") (pintype "passive"))
      (node (ref "IC4") (pin "13") (pinfunction "-IN_13") (pintype "input"))
      (node (ref "R34") (pin "2") (pinfunction "2_2") (pintype "passive"))
      (node (ref "R36") (pin "1") (pinfunction "1_1") (pintype "passive"))
      (node (ref "R38") (pin "1") (pinfunction "1_1") (pintype "passive"))
    )
    (net (code "79") (name "Net-(R3-A)") (class "Default")
      (node (ref "R2") (pin "2") (pinfunction "2_2") (pintype "passive"))
      (node (ref "R3") (pin "3") (pinfunction "A_3") (pintype "passive"))
    )
    (net (code "80") (name "Net-(R11-A)") (class "Default")
      (node (ref "R11") (pin "3") (pinfunction "A_3") (pintype "passive"))
      (node (ref "R6") (pin "2") (pinfunction "2_2") (pintype "passive"))
    )
    (net (code "81") (name "Net-(R32-S)") (class "Default")
      (node (ref "C22") (pin "-") (pinfunction "-_-") (pintype "passive"))
      (node (ref "R32") (pin "2") (pinfunction "S_2") (pintype "passive"))
    )
    (net (code "82") (name "Net-(R33-S)") (class "Default")
      (node (ref "C24") (pin "-") (pinfunction "-_-") (pintype "passive"))
      (node (ref "R33") (pin "2") (pinfunction "S_2") (pintype "passive"))
    )
    (net (code "83") (name "OUT1") (class "Default")
      (node (ref "JP5-AUDIO") (pin "3") (pinfunction "3_3") (pintype "passive"))
      (node (ref "R4") (pin "1") (pinfunction "1_1") (pintype "passive"))
    )
    (net (code "84") (name "OUT2") (class "Default")
      (node (ref "JP5-AUDIO") (pin "2") (pinfunction "2_2") (pintype "passive"))
      (node (ref "R12") (pin "1") (pinfunction "1_1") (pintype "passive"))
    )
    (net (code "85") (name "RIN+") (class "Default")
      (node (ref "AXOLOTICORE") (pin "RIN+") (pinfunction "RIN+_RIN+") (pintype "bidirectional"))
      (node (ref "C24") (pin "+") (pinfunction "+_+") (pintype "passive"))
    )
    (net (code "86") (name "SCK") (class "Default")
      (node (ref "AXOLOTICORE") (pin "PA5") (pinfunction "PA5_PA5") (pintype "bidirectional"))
      (node (ref "JP3") (pin "8") (pinfunction "8_8") (pintype "passive"))
      (node (ref "JP4") (pin "8") (pinfunction "8_8") (pintype "passive"))
      (node (ref "U$4") (pin "P$13") (pinfunction "CLK_P$13") (pintype "bidirectional"))
      (node (ref "U$5") (pin "P$13") (pinfunction "CLK_P$13") (pintype "bidirectional"))
    )
    (net (code "87") (name "VBUS") (class "Default")
      (node (ref "AXOLOTICORE") (pin "VBUS") (pinfunction "VBUS_VBUS") (pintype "bidirectional"))
      (node (ref "C25") (pin "1") (pinfunction "1_1") (pintype "passive"))
      (node (ref "D4") (pin "C") (pinfunction "C_C") (pintype "passive"))
      (node (ref "R40") (pin "2") (pinfunction "2_2") (pintype "passive"))
      (node (ref "R41") (pin "1") (pinfunction "1_1") (pintype "passive"))
    )
    (net (code "88") (name "VCC") (class "Default")
      (node (ref "C1") (pin "+") (pinfunction "+_+") (pintype "passive"))
      (node (ref "C2") (pin "+") (pinfunction "+_+") (pintype "passive"))
      (node (ref "C6") (pin "1") (pinfunction "1_1") (pintype "passive"))
      (node (ref "IC1") (pin "IN") (pinfunction "IN_IN") (pintype "input"))
      (node (ref "IC2") (pin "4") (pinfunction "V+_4") (pintype "power_in"))
      (node (ref "JP1") (pin "1") (pinfunction "1_1") (pintype "passive"))
      (node (ref "L2") (pin "1") (pinfunction "1_1") (pintype "passive"))
      (node (ref "R40") (pin "1") (pinfunction "1_1") (pintype "passive"))
    )
    (net (code "89") (name "VDD") (class "Default")
      (node (ref "AXOLOTICORE") (pin "VDD1") (pinfunction "VDD1_VDD1") (pintype "bidirectional"))
      (node (ref "C12") (pin "1") (pinfunction "1_1") (pintype "passive"))
      (node (ref "C14") (pin "+") (pinfunction "+_+") (pintype "passive"))
      (node (ref "C5") (pin "1") (pinfunction "1_1") (pintype "passive"))
      (node (ref "C8") (pin "+") (pinfunction "+_+") (pintype "passive"))
      (node (ref "JP3") (pin "24") (pinfunction "24_24") (pintype "passive"))
      (node (ref "JP4") (pin "24") (pinfunction "24_24") (pintype "passive"))
      (node (ref "JP_POT") (pin "1") (pinfunction "1_1") (pintype "passive"))
      (node (ref "U$4") (pin "P$15") (pinfunction "VREF_P$15") (pintype "bidirectional"))
      (node (ref "U$4") (pin "P$16") (pinfunction "VDD_P$16") (pintype "bidirectional"))
      (node (ref "U$5") (pin "P$15") (pinfunction "VREF_P$15") (pintype "bidirectional"))
      (node (ref "U$5") (pin "P$16") (pinfunction "VDD_P$16") (pintype "bidirectional"))
    )
    (net (code "90") (name "VEE") (class "Default")
      (node (ref "C13") (pin "-") (pinfunction "-_-") (pintype "passive"))
      (node (ref "C7") (pin "2") (pinfunction "2_2") (pintype "passive"))
      (node (ref "IC2") (pin "11") (pinfunction "V-_11") (pintype "power_in"))
      (node (ref "L1") (pin "1") (pinfunction "1_1") (pintype "passive"))
      (node (ref "R30") (pin "1") (pinfunction "1_1") (pintype "passive"))
    )
    (net (code "91") (name "unconnected-(AXOLOTICORE-PadGND4)") (class "Default")
      (node (ref "AXOLOTICORE") (pin "GND4") (pinfunction "GND4_GND4") (pintype "bidirectional"))
    )
    (net (code "92") (name "unconnected-(AXOLOTICORE-PadGND5)") (class "Default")
      (node (ref "AXOLOTICORE") (pin "GND5") (pinfunction "GND5_GND5") (pintype "bidirectional"))
    )
    (net (code "93") (name "unconnected-(AXOLOTICORE-PadLIN-)") (class "Default")
      (node (ref "AXOLOTICORE") (pin "LIN-") (pinfunction "LIN-_LIN-") (pintype "bidirectional"))
    )
    (net (code "94") (name "unconnected-(AXOLOTICORE-PadRIN-)") (class "Default")
      (node (ref "AXOLOTICORE") (pin "RIN-") (pinfunction "RIN-_RIN-") (pintype "bidirectional"))
    )
    (net (code "95") (name "unconnected-(AXOLOTICOREB-RX-PadUARTRX)") (class "Default")
      (node (ref "AXOLOTICORE") (pin "UARTRX") (pinfunction "RX_UARTRX") (pintype "bidirectional"))
    )
    (net (code "96") (name "unconnected-(AXOLOTICOREB-TX-PadUARTTX)") (class "Default")
      (node (ref "AXOLOTICORE") (pin "UARTTX") (pinfunction "TX_UARTTX") (pintype "bidirectional"))
    )
  )
)
